# Sensor_Cameralink_TRX.net
KiCad netlist of a schematic drawn in EAGLE
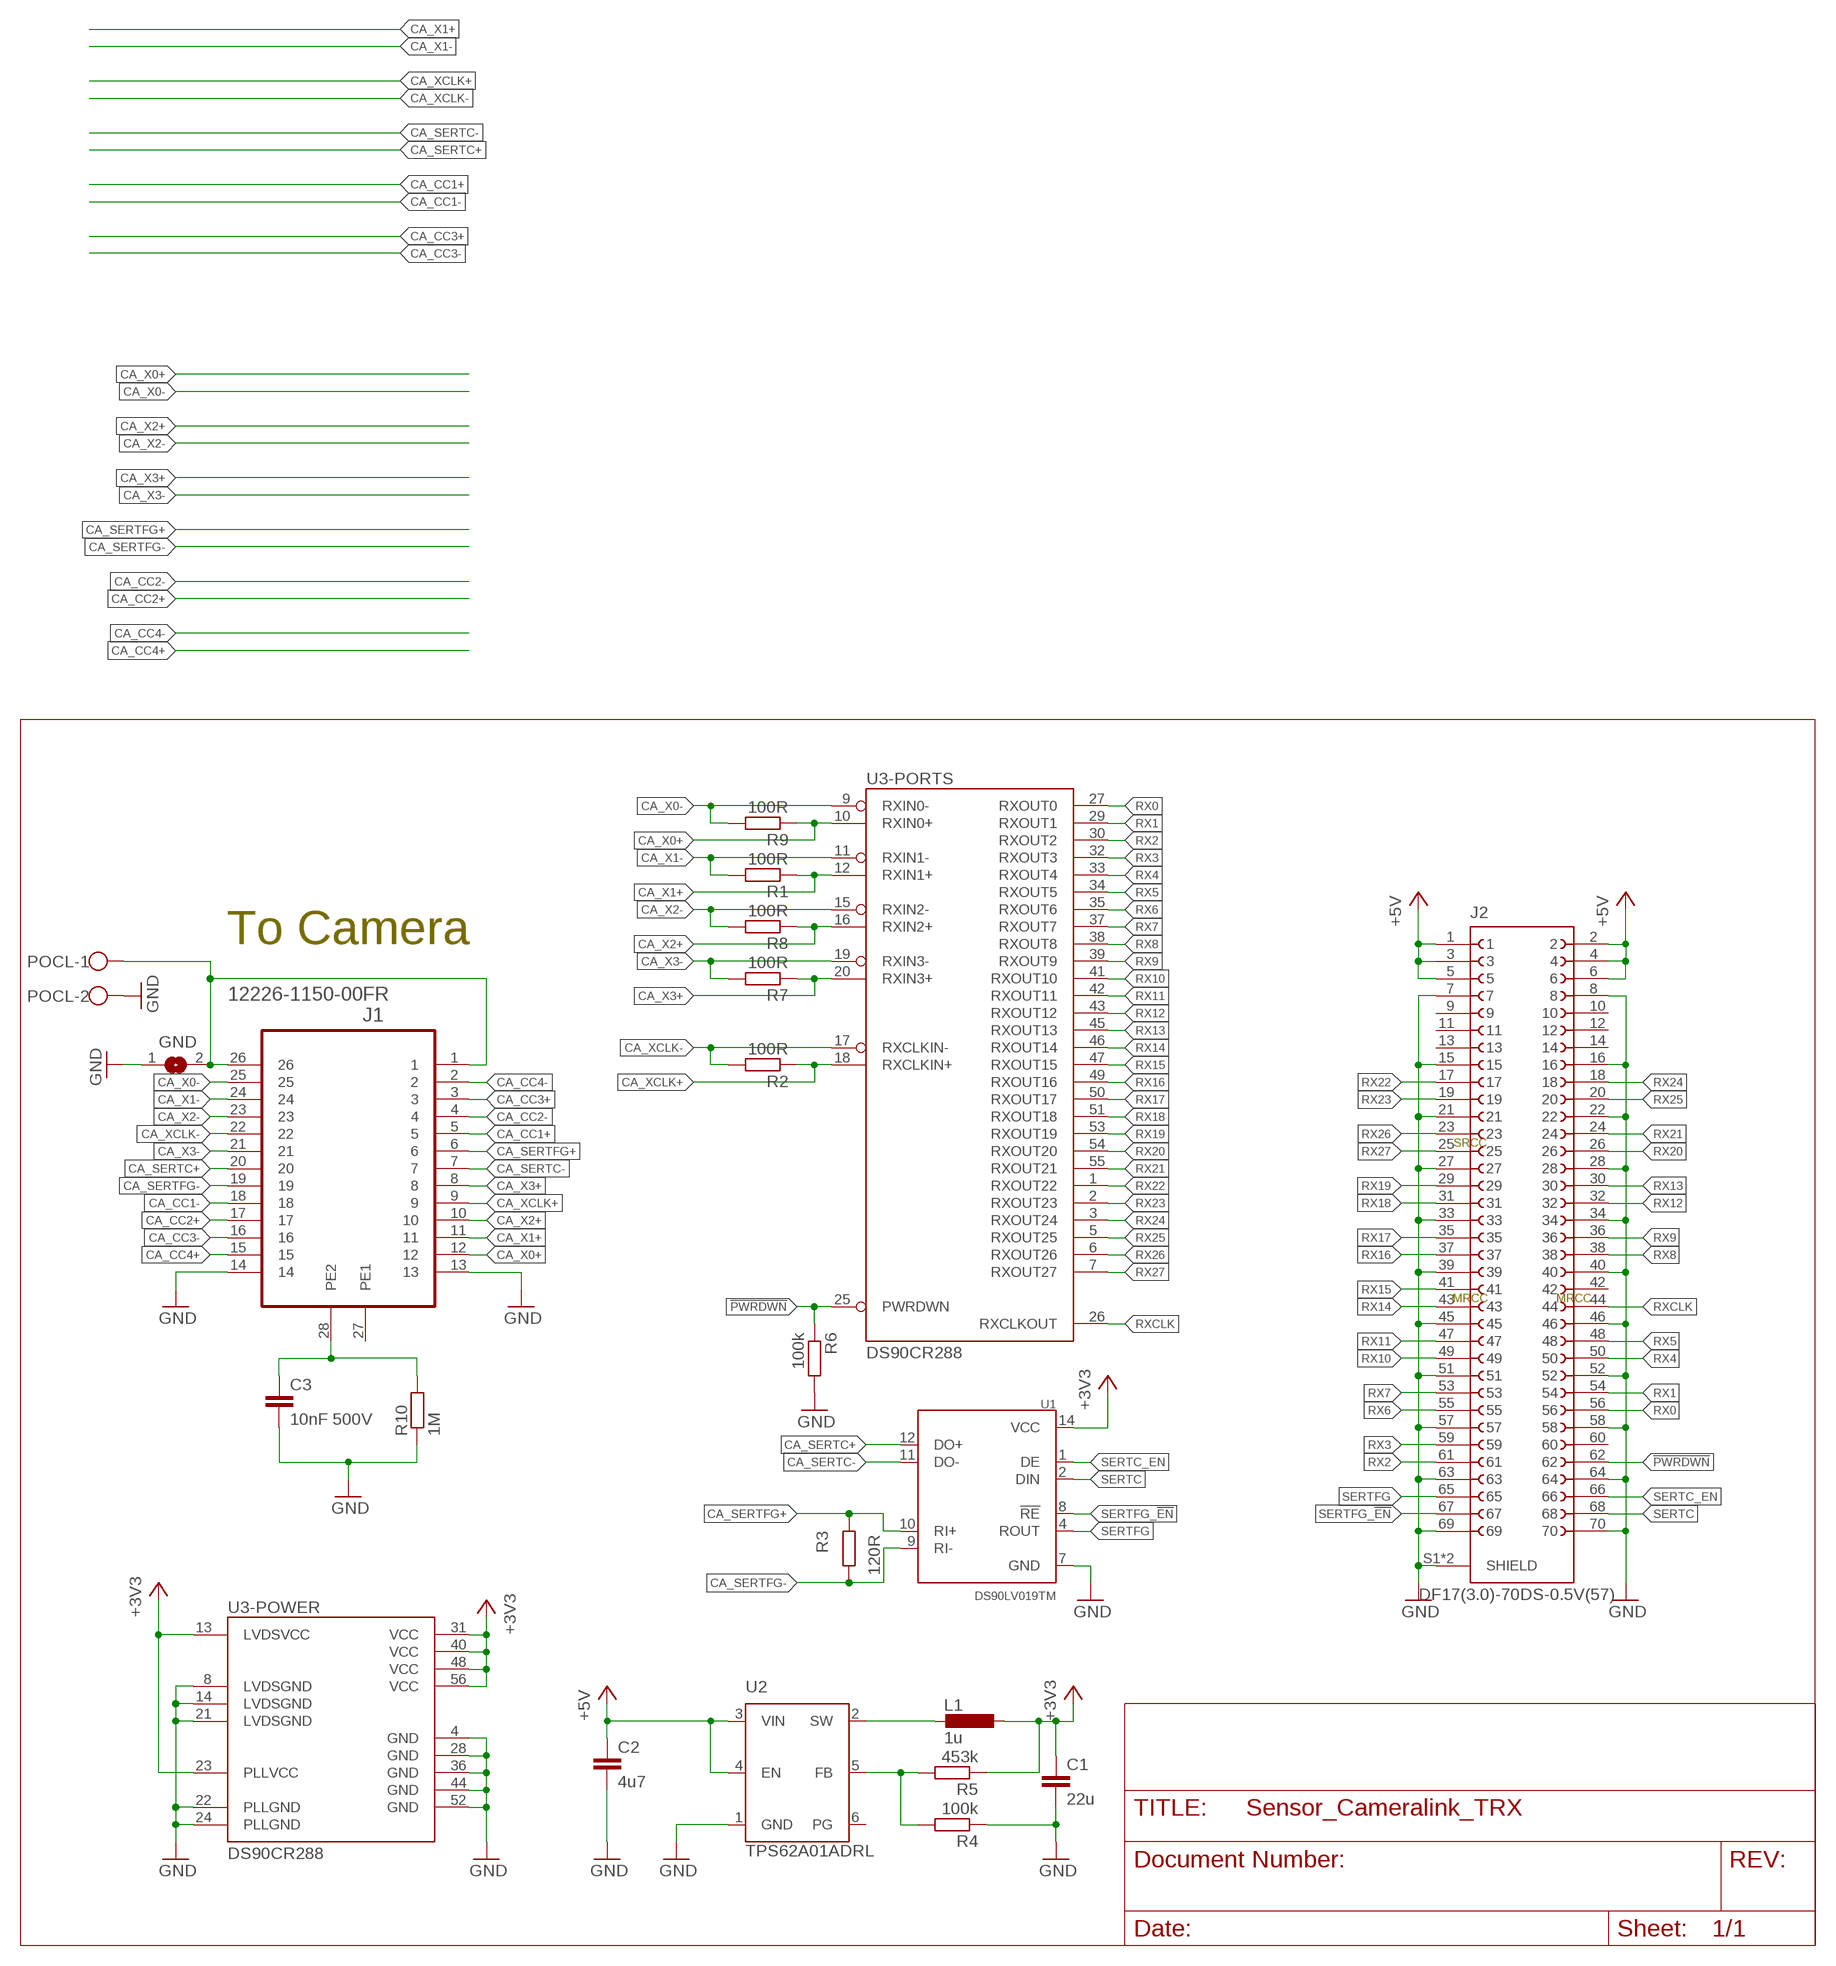
[diagram p0: schematic, sheet 1]

(export (version "E")
  (design (tool "Eeschema 10.0.6"))
  (components
    (comp (ref "C1")
      (value "22u")
      (footprint "eagle-import:C0603")
      (libsource (lib "eagle-import") (part "C-EUC0603"))
    )
    (comp (ref "C2")
      (value "4u7")
      (footprint "eagle-import:C0603")
      (libsource (lib "eagle-import") (part "C-EUC0603"))
    )
    (comp (ref "C3")
      (value "10nF 500V")
      (footprint "eagle-import:C0805")
      (libsource (lib "eagle-import") (part "C-EUC0805"))
    )
    (comp (ref "GND") (value "SJ") (footprint "eagle-import:SJ") (libsource (lib "eagle-import") (part "SJ")))
    (comp (ref "J1")
      (value "12226-1150-00FR")
      (footprint "eagle-import:3M_12226-1150-00FR")
      (libsource (lib "eagle-import") (part "12226-1150-00FR"))
    )
    (comp (ref "J2")
      (value "DF17(3.0)-70DS-0.5V(57)")
      (footprint "eagle-import:DF17(3.0)-70DS-0.5V(57)")
      (libsource (lib "eagle-import") (part "DF17(3.0)-70DS-0.5V(57)"))
    )
    (comp (ref "L1")
      (value "1u")
      (footprint "eagle-import:L1008")
      (fields (field (name "MPN") "LQM2HPN1R0MG0L"))
      (libsource (lib "eagle-import") (part "L-EU1008"))
    )
    (comp (ref "POCL")
      (value "W237-102")
      (footprint "eagle-import:W237-102")
      (fields (field (name "MPN") "237-102"))
      (libsource (lib "eagle-import") (part "W237-102"))
    )
    (comp (ref "R1")
      (value "100R")
      (footprint "eagle-import:R0402")
      (libsource (lib "eagle-import") (part "R-EU_R0402"))
    )
    (comp (ref "R2")
      (value "100R")
      (footprint "eagle-import:R0402")
      (libsource (lib "eagle-import") (part "R-EU_R0402"))
    )
    (comp (ref "R3")
      (value "120R")
      (footprint "eagle-import:R0402")
      (libsource (lib "eagle-import") (part "R-EU_R0402"))
    )
    (comp (ref "R4")
      (value "100k")
      (footprint "eagle-import:R0402")
      (libsource (lib "eagle-import") (part "R-EU_R0402"))
    )
    (comp (ref "R5")
      (value "453k")
      (footprint "eagle-import:R0402")
      (libsource (lib "eagle-import") (part "R-EU_R0402"))
    )
    (comp (ref "R6")
      (value "100k")
      (footprint "eagle-import:R0402")
      (libsource (lib "eagle-import") (part "R-EU_R0402"))
    )
    (comp (ref "R7")
      (value "100R")
      (footprint "eagle-import:R0402")
      (libsource (lib "eagle-import") (part "R-EU_R0402"))
    )
    (comp (ref "R8")
      (value "100R")
      (footprint "eagle-import:R0402")
      (libsource (lib "eagle-import") (part "R-EU_R0402"))
    )
    (comp (ref "R9")
      (value "100R")
      (footprint "eagle-import:R0402")
      (libsource (lib "eagle-import") (part "R-EU_R0402"))
    )
    (comp (ref "R10")
      (value "1M")
      (footprint "eagle-import:R0805")
      (libsource (lib "eagle-import") (part "resistor_R-EU_R0805"))
    )
    (comp (ref "U1")
      (value "DS90LV019TM")
      (footprint "eagle-import:SO-14")
      (libsource (lib "eagle-import") (part "DS90LV019TM"))
    )
    (comp (ref "U2")
      (value "TPS62A01ADRL")
      (footprint "eagle-import:SOTFL50P160X60-6N")
      (fields (field (name "MANUFACTURER_PART_NUMBER") "TPS62A01ADRLR"))
      (libsource (lib "eagle-import") (part "TPS62A01ADRL"))
    )
    (comp (ref "U3")
      (value "DS90CR288")
      (footprint "eagle-import:HTSSOP56")
      (libsource (lib "eagle-import") (part "DS90CR288"))
    )
  )
  (nets
    (net (code "1") (name "+3V3") (class "Default")
      (node (ref "C1") (pin "1") (pinfunction "1_1") (pintype "passive"))
      (node (ref "L1") (pin "1") (pinfunction "1_1") (pintype "passive"))
      (node (ref "R5") (pin "1") (pinfunction "1_1") (pintype "passive"))
      (node (ref "U1") (pin "14") (pinfunction "VCC_14") (pintype "power_in"))
      (node (ref "U3") (pin "13") (pinfunction "LVDSVCC_13") (pintype "bidirectional"))
      (node (ref "U3") (pin "23") (pinfunction "PLLVCC_23") (pintype "bidirectional"))
      (node (ref "U3") (pin "31") (pinfunction "VCC_31") (pintype "bidirectional"))
      (node (ref "U3") (pin "40") (pinfunction "VCC_40") (pintype "bidirectional"))
      (node (ref "U3") (pin "48") (pinfunction "VCC_48") (pintype "bidirectional"))
      (node (ref "U3") (pin "56") (pinfunction "VCC_56") (pintype "bidirectional"))
    )
    (net (code "2") (name "+5V") (class "Default")
      (node (ref "C2") (pin "1") (pinfunction "1_1") (pintype "passive"))
      (node (ref "J2") (pin "1") (pinfunction "1_1") (pintype "passive"))
      (node (ref "J2") (pin "2") (pinfunction "2_2") (pintype "passive"))
      (node (ref "J2") (pin "3") (pinfunction "3_3") (pintype "passive"))
      (node (ref "J2") (pin "4") (pinfunction "4_4") (pintype "passive"))
      (node (ref "J2") (pin "5") (pinfunction "5_5") (pintype "passive"))
      (node (ref "J2") (pin "6") (pinfunction "6_6") (pintype "passive"))
      (node (ref "U2") (pin "3") (pinfunction "VIN_3") (pintype "bidirectional"))
      (node (ref "U2") (pin "4") (pinfunction "EN_4") (pintype "bidirectional"))
    )
    (net (code "3") (name "/SERTFG_~{EN}") (class "Default")
      (node (ref "J2") (pin "67") (pinfunction "67_67") (pintype "passive"))
      (node (ref "U1") (pin "8") (pinfunction "~{RE}_8") (pintype "input"))
    )
    (net (code "4") (name "/~{PWRDWN}") (class "Default")
      (node (ref "J2") (pin "62") (pinfunction "62_62") (pintype "passive"))
      (node (ref "R6") (pin "1") (pinfunction "1_1") (pintype "passive"))
      (node (ref "U3") (pin "25") (pinfunction "PWRDWN_25") (pintype "bidirectional"))
    )
    (net (code "5") (name "CA_CC1+") (class "Default")
      (node (ref "J1") (pin "5") (pinfunction "5_5") (pintype "passive"))
    )
    (net (code "6") (name "CA_CC1-") (class "Default")
      (node (ref "J1") (pin "18") (pinfunction "18_18") (pintype "passive"))
    )
    (net (code "7") (name "CA_CC2+") (class "Default")
      (node (ref "J1") (pin "17") (pinfunction "17_17") (pintype "passive"))
    )
    (net (code "8") (name "CA_CC2-") (class "Default")
      (node (ref "J1") (pin "4") (pinfunction "4_4") (pintype "passive"))
    )
    (net (code "9") (name "CA_CC3+") (class "Default")
      (node (ref "J1") (pin "3") (pinfunction "3_3") (pintype "passive"))
    )
    (net (code "10") (name "CA_CC3-") (class "Default")
      (node (ref "J1") (pin "16") (pinfunction "16_16") (pintype "passive"))
    )
    (net (code "11") (name "CA_CC4+") (class "Default")
      (node (ref "J1") (pin "15") (pinfunction "15_15") (pintype "passive"))
    )
    (net (code "12") (name "CA_CC4-") (class "Default")
      (node (ref "J1") (pin "2") (pinfunction "2_2") (pintype "passive"))
    )
    (net (code "13") (name "CA_SERTC+") (class "Default")
      (node (ref "J1") (pin "20") (pinfunction "20_20") (pintype "passive"))
      (node (ref "U1") (pin "12") (pinfunction "DO+_12") (pintype "output"))
    )
    (net (code "14") (name "CA_SERTC-") (class "Default")
      (node (ref "J1") (pin "7") (pinfunction "7_7") (pintype "passive"))
      (node (ref "U1") (pin "11") (pinfunction "DO-_11") (pintype "output"))
    )
    (net (code "15") (name "CA_SERTFG+") (class "Default")
      (node (ref "J1") (pin "6") (pinfunction "6_6") (pintype "passive"))
      (node (ref "R3") (pin "1") (pinfunction "1_1") (pintype "passive"))
      (node (ref "U1") (pin "10") (pinfunction "RI+_10") (pintype "input"))
    )
    (net (code "16") (name "CA_SERTFG-") (class "Default")
      (node (ref "J1") (pin "19") (pinfunction "19_19") (pintype "passive"))
      (node (ref "R3") (pin "2") (pinfunction "2_2") (pintype "passive"))
      (node (ref "U1") (pin "9") (pinfunction "RI-_9") (pintype "input"))
    )
    (net (code "17") (name "CA_X0+") (class "Default")
      (node (ref "J1") (pin "12") (pinfunction "12_12") (pintype "passive"))
      (node (ref "R9") (pin "1") (pinfunction "1_1") (pintype "passive"))
      (node (ref "U3") (pin "10") (pinfunction "RXIN0+_10") (pintype "bidirectional"))
    )
    (net (code "18") (name "CA_X0-") (class "Default")
      (node (ref "J1") (pin "25") (pinfunction "25_25") (pintype "passive"))
      (node (ref "R9") (pin "2") (pinfunction "2_2") (pintype "passive"))
      (node (ref "U3") (pin "9") (pinfunction "RXIN0-_9") (pintype "bidirectional"))
    )
    (net (code "19") (name "CA_X1+") (class "Default")
      (node (ref "J1") (pin "11") (pinfunction "11_11") (pintype "passive"))
      (node (ref "R1") (pin "1") (pinfunction "1_1") (pintype "passive"))
      (node (ref "U3") (pin "12") (pinfunction "RXIN1+_12") (pintype "bidirectional"))
    )
    (net (code "20") (name "CA_X1-") (class "Default")
      (node (ref "J1") (pin "24") (pinfunction "24_24") (pintype "passive"))
      (node (ref "R1") (pin "2") (pinfunction "2_2") (pintype "passive"))
      (node (ref "U3") (pin "11") (pinfunction "RXIN1-_11") (pintype "bidirectional"))
    )
    (net (code "21") (name "CA_X2+") (class "Default")
      (node (ref "J1") (pin "10") (pinfunction "10_10") (pintype "passive"))
      (node (ref "R8") (pin "1") (pinfunction "1_1") (pintype "passive"))
      (node (ref "U3") (pin "16") (pinfunction "RXIN2+_16") (pintype "bidirectional"))
    )
    (net (code "22") (name "CA_X2-") (class "Default")
      (node (ref "J1") (pin "23") (pinfunction "23_23") (pintype "passive"))
      (node (ref "R8") (pin "2") (pinfunction "2_2") (pintype "passive"))
      (node (ref "U3") (pin "15") (pinfunction "RXIN2-_15") (pintype "bidirectional"))
    )
    (net (code "23") (name "CA_X3+") (class "Default")
      (node (ref "J1") (pin "8") (pinfunction "8_8") (pintype "passive"))
      (node (ref "R7") (pin "1") (pinfunction "1_1") (pintype "passive"))
      (node (ref "U3") (pin "20") (pinfunction "RXIN3+_20") (pintype "bidirectional"))
    )
    (net (code "24") (name "CA_X3-") (class "Default")
      (node (ref "J1") (pin "21") (pinfunction "21_21") (pintype "passive"))
      (node (ref "R7") (pin "2") (pinfunction "2_2") (pintype "passive"))
      (node (ref "U3") (pin "19") (pinfunction "RXIN3-_19") (pintype "bidirectional"))
    )
    (net (code "25") (name "CA_XCLK+") (class "Default")
      (node (ref "J1") (pin "9") (pinfunction "9_9") (pintype "passive"))
      (node (ref "R2") (pin "1") (pinfunction "1_1") (pintype "passive"))
      (node (ref "U3") (pin "18") (pinfunction "RXCLKIN+_18") (pintype "bidirectional"))
    )
    (net (code "26") (name "CA_XCLK-") (class "Default")
      (node (ref "J1") (pin "22") (pinfunction "22_22") (pintype "passive"))
      (node (ref "R2") (pin "2") (pinfunction "2_2") (pintype "passive"))
      (node (ref "U3") (pin "17") (pinfunction "RXCLKIN-_17") (pintype "bidirectional"))
    )
    (net (code "27") (name "GND") (class "Default")
      (node (ref "C1") (pin "2") (pinfunction "2_2") (pintype "passive"))
      (node (ref "C2") (pin "2") (pinfunction "2_2") (pintype "passive"))
      (node (ref "C3") (pin "2") (pinfunction "2_2") (pintype "passive"))
      (node (ref "GND") (pin "1") (pinfunction "1_1") (pintype "passive"))
      (node (ref "J1") (pin "13") (pinfunction "13_13") (pintype "passive"))
      (node (ref "J1") (pin "14") (pinfunction "14_14") (pintype "passive"))
      (node (ref "J2") (pin "15") (pinfunction "15_15") (pintype "passive"))
      (node (ref "J2") (pin "16") (pinfunction "16_16") (pintype "passive"))
      (node (ref "J2") (pin "21") (pinfunction "21_21") (pintype "passive"))
      (node (ref "J2") (pin "22") (pinfunction "22_22") (pintype "passive"))
      (node (ref "J2") (pin "27") (pinfunction "27_27") (pintype "passive"))
      (node (ref "J2") (pin "28") (pinfunction "28_28") (pintype "passive"))
      (node (ref "J2") (pin "33") (pinfunction "33_33") (pintype "passive"))
      (node (ref "J2") (pin "34") (pinfunction "34_34") (pintype "passive"))
      (node (ref "J2") (pin "39") (pinfunction "39_39") (pintype "passive"))
      (node (ref "J2") (pin "40") (pinfunction "40_40") (pintype "passive"))
      (node (ref "J2") (pin "45") (pinfunction "45_45") (pintype "passive"))
      (node (ref "J2") (pin "46") (pinfunction "46_46") (pintype "passive"))
      (node (ref "J2") (pin "51") (pinfunction "51_51") (pintype "passive"))
      (node (ref "J2") (pin "52") (pinfunction "52_52") (pintype "passive"))
      (node (ref "J2") (pin "57") (pinfunction "57_57") (pintype "passive"))
      (node (ref "J2") (pin "58") (pinfunction "58_58") (pintype "passive"))
      (node (ref "J2") (pin "63") (pinfunction "63_63") (pintype "passive"))
      (node (ref "J2") (pin "64") (pinfunction "64_64") (pintype "passive"))
      (node (ref "J2") (pin "69") (pinfunction "69_69") (pintype "passive"))
      (node (ref "J2") (pin "7") (pinfunction "7_7") (pintype "passive"))
      (node (ref "J2") (pin "70") (pinfunction "70_70") (pintype "passive"))
      (node (ref "J2") (pin "8") (pinfunction "8_8") (pintype "passive"))
      (node (ref "J2") (pin "S1") (pinfunction "SHIELD_S1") (pintype "passive"))
      (node (ref "J2") (pin "S2") (pinfunction "SHIELD_S2") (pintype "passive"))
      (node (ref "POCL") (pin "2") (pinfunction "KL_2") (pintype "passive"))
      (node (ref "R10") (pin "1") (pinfunction "1_1") (pintype "passive"))
      (node (ref "R4") (pin "1") (pinfunction "1_1") (pintype "passive"))
      (node (ref "R6") (pin "2") (pinfunction "2_2") (pintype "passive"))
      (node (ref "U1") (pin "7") (pinfunction "GND_7") (pintype "power_in"))
      (node (ref "U2") (pin "1") (pinfunction "GND_1") (pintype "bidirectional"))
      (node (ref "U3") (pin "14") (pinfunction "LVDSGND_14") (pintype "bidirectional"))
      (node (ref "U3") (pin "21") (pinfunction "LVDSGND_21") (pintype "bidirectional"))
      (node (ref "U3") (pin "22") (pinfunction "PLLGND_22") (pintype "bidirectional"))
      (node (ref "U3") (pin "24") (pinfunction "PLLGND_24") (pintype "bidirectional"))
      (node (ref "U3") (pin "28") (pinfunction "GND_28") (pintype "bidirectional"))
      (node (ref "U3") (pin "36") (pinfunction "GND_36") (pintype "bidirectional"))
      (node (ref "U3") (pin "4") (pinfunction "GND_4") (pintype "bidirectional"))
      (node (ref "U3") (pin "44") (pinfunction "GND_44") (pintype "bidirectional"))
      (node (ref "U3") (pin "52") (pinfunction "GND_52") (pintype "bidirectional"))
      (node (ref "U3") (pin "8") (pinfunction "LVDSGND_8") (pintype "bidirectional"))
    )
    (net (code "28") (name "Net-(J1-PE2)") (class "Default")
      (node (ref "C3") (pin "1") (pinfunction "1_1") (pintype "passive"))
      (node (ref "J1") (pin "28") (pinfunction "PE2_28") (pintype "bidirectional"))
      (node (ref "R10") (pin "2") (pinfunction "2_2") (pintype "passive"))
    )
    (net (code "29") (name "Net-(POCLA-KL)") (class "Default")
      (node (ref "GND") (pin "2") (pinfunction "2_2") (pintype "passive"))
      (node (ref "J1") (pin "1") (pinfunction "1_1") (pintype "passive"))
      (node (ref "J1") (pin "26") (pinfunction "26_26") (pintype "passive"))
      (node (ref "POCL") (pin "1") (pinfunction "KL_1") (pintype "passive"))
    )
    (net (code "30") (name "Net-(U2-FB)") (class "Default")
      (node (ref "R4") (pin "2") (pinfunction "2_2") (pintype "passive"))
      (node (ref "R5") (pin "2") (pinfunction "2_2") (pintype "passive"))
      (node (ref "U2") (pin "5") (pinfunction "FB_5") (pintype "bidirectional"))
    )
    (net (code "31") (name "Net-(U2-SW)") (class "Default")
      (node (ref "L1") (pin "2") (pinfunction "2_2") (pintype "passive"))
      (node (ref "U2") (pin "2") (pinfunction "SW_2") (pintype "bidirectional"))
    )
    (net (code "32") (name "RX0") (class "Default")
      (node (ref "J2") (pin "56") (pinfunction "56_56") (pintype "passive"))
      (node (ref "U3") (pin "27") (pinfunction "RXOUT0_27") (pintype "bidirectional"))
    )
    (net (code "33") (name "RX1") (class "Default")
      (node (ref "J2") (pin "54") (pinfunction "54_54") (pintype "passive"))
      (node (ref "U3") (pin "29") (pinfunction "RXOUT1_29") (pintype "bidirectional"))
    )
    (net (code "34") (name "RX2") (class "Default")
      (node (ref "J2") (pin "61") (pinfunction "61_61") (pintype "passive"))
      (node (ref "U3") (pin "30") (pinfunction "RXOUT2_30") (pintype "bidirectional"))
    )
    (net (code "35") (name "RX3") (class "Default")
      (node (ref "J2") (pin "59") (pinfunction "59_59") (pintype "passive"))
      (node (ref "U3") (pin "32") (pinfunction "RXOUT3_32") (pintype "bidirectional"))
    )
    (net (code "36") (name "RX4") (class "Default")
      (node (ref "J2") (pin "50") (pinfunction "50_50") (pintype "passive"))
      (node (ref "U3") (pin "33") (pinfunction "RXOUT4_33") (pintype "bidirectional"))
    )
    (net (code "37") (name "RX5") (class "Default")
      (node (ref "J2") (pin "48") (pinfunction "48_48") (pintype "passive"))
      (node (ref "U3") (pin "34") (pinfunction "RXOUT5_34") (pintype "bidirectional"))
    )
    (net (code "38") (name "RX6") (class "Default")
      (node (ref "J2") (pin "55") (pinfunction "55_55") (pintype "passive"))
      (node (ref "U3") (pin "35") (pinfunction "RXOUT6_35") (pintype "bidirectional"))
    )
    (net (code "39") (name "RX7") (class "Default")
      (node (ref "J2") (pin "53") (pinfunction "53_53") (pintype "passive"))
      (node (ref "U3") (pin "37") (pinfunction "RXOUT7_37") (pintype "bidirectional"))
    )
    (net (code "40") (name "RX8") (class "Default")
      (node (ref "J2") (pin "38") (pinfunction "38_38") (pintype "passive"))
      (node (ref "U3") (pin "38") (pinfunction "RXOUT8_38") (pintype "bidirectional"))
    )
    (net (code "41") (name "RX9") (class "Default")
      (node (ref "J2") (pin "36") (pinfunction "36_36") (pintype "passive"))
      (node (ref "U3") (pin "39") (pinfunction "RXOUT9_39") (pintype "bidirectional"))
    )
    (net (code "42") (name "RX10") (class "Default")
      (node (ref "J2") (pin "49") (pinfunction "49_49") (pintype "passive"))
      (node (ref "U3") (pin "41") (pinfunction "RXOUT10_41") (pintype "bidirectional"))
    )
    (net (code "43") (name "RX11") (class "Default")
      (node (ref "J2") (pin "47") (pinfunction "47_47") (pintype "passive"))
      (node (ref "U3") (pin "42") (pinfunction "RXOUT11_42") (pintype "bidirectional"))
    )
    (net (code "44") (name "RX12") (class "Default")
      (node (ref "J2") (pin "32") (pinfunction "32_32") (pintype "passive"))
      (node (ref "U3") (pin "43") (pinfunction "RXOUT12_43") (pintype "bidirectional"))
    )
    (net (code "45") (name "RX13") (class "Default")
      (node (ref "J2") (pin "30") (pinfunction "30_30") (pintype "passive"))
      (node (ref "U3") (pin "45") (pinfunction "RXOUT13_45") (pintype "bidirectional"))
    )
    (net (code "46") (name "RX14") (class "Default")
      (node (ref "J2") (pin "43") (pinfunction "43_43") (pintype "passive"))
      (node (ref "U3") (pin "46") (pinfunction "RXOUT14_46") (pintype "bidirectional"))
    )
    (net (code "47") (name "RX15") (class "Default")
      (node (ref "J2") (pin "41") (pinfunction "41_41") (pintype "passive"))
      (node (ref "U3") (pin "47") (pinfunction "RXOUT15_47") (pintype "bidirectional"))
    )
    (net (code "48") (name "RX16") (class "Default")
      (node (ref "J2") (pin "37") (pinfunction "37_37") (pintype "passive"))
      (node (ref "U3") (pin "49") (pinfunction "RXOUT16_49") (pintype "bidirectional"))
    )
    (net (code "49") (name "RX17") (class "Default")
      (node (ref "J2") (pin "35") (pinfunction "35_35") (pintype "passive"))
      (node (ref "U3") (pin "50") (pinfunction "RXOUT17_50") (pintype "bidirectional"))
    )
    (net (code "50") (name "RX18") (class "Default")
      (node (ref "J2") (pin "31") (pinfunction "31_31") (pintype "passive"))
      (node (ref "U3") (pin "51") (pinfunction "RXOUT18_51") (pintype "bidirectional"))
    )
    (net (code "51") (name "RX19") (class "Default")
      (node (ref "J2") (pin "29") (pinfunction "29_29") (pintype "passive"))
      (node (ref "U3") (pin "53") (pinfunction "RXOUT19_53") (pintype "bidirectional"))
    )
    (net (code "52") (name "RX20") (class "Default")
      (node (ref "J2") (pin "26") (pinfunction "26_26") (pintype "passive"))
      (node (ref "U3") (pin "54") (pinfunction "RXOUT20_54") (pintype "bidirectional"))
    )
    (net (code "53") (name "RX21") (class "Default")
      (node (ref "J2") (pin "24") (pinfunction "24_24") (pintype "passive"))
      (node (ref "U3") (pin "55") (pinfunction "RXOUT21_55") (pintype "bidirectional"))
    )
    (net (code "54") (name "RX22") (class "Default")
      (node (ref "J2") (pin "17") (pinfunction "17_17") (pintype "passive"))
      (node (ref "U3") (pin "1") (pinfunction "RXOUT22_1") (pintype "bidirectional"))
    )
    (net (code "55") (name "RX23") (class "Default")
      (node (ref "J2") (pin "19") (pinfunction "19_19") (pintype "passive"))
      (node (ref "U3") (pin "2") (pinfunction "RXOUT23_2") (pintype "bidirectional"))
    )
    (net (code "56") (name "RX24") (class "Default")
      (node (ref "J2") (pin "18") (pinfunction "18_18") (pintype "passive"))
      (node (ref "U3") (pin "3") (pinfunction "RXOUT24_3") (pintype "bidirectional"))
    )
    (net (code "57") (name "RX25") (class "Default")
      (node (ref "J2") (pin "20") (pinfunction "20_20") (pintype "passive"))
      (node (ref "U3") (pin "5") (pinfunction "RXOUT25_5") (pintype "bidirectional"))
    )
    (net (code "58") (name "RX26") (class "Default")
      (node (ref "J2") (pin "23") (pinfunction "23_23") (pintype "passive"))
      (node (ref "U3") (pin "6") (pinfunction "RXOUT26_6") (pintype "bidirectional"))
    )
    (net (code "59") (name "RX27") (class "Default")
      (node (ref "J2") (pin "25") (pinfunction "25_25") (pintype "passive"))
      (node (ref "U3") (pin "7") (pinfunction "RXOUT27_7") (pintype "bidirectional"))
    )
    (net (code "60") (name "RXCLK") (class "Default")
      (node (ref "J2") (pin "44") (pinfunction "44_44") (pintype "passive"))
      (node (ref "U3") (pin "26") (pinfunction "RXCLKOUT_26") (pintype "bidirectional"))
    )
    (net (code "61") (name "SERTC") (class "Default")
      (node (ref "J2") (pin "68") (pinfunction "68_68") (pintype "passive"))
      (node (ref "U1") (pin "2") (pinfunction "DIN_2") (pintype "input"))
    )
    (net (code "62") (name "SERTC_EN") (class "Default")
      (node (ref "J2") (pin "66") (pinfunction "66_66") (pintype "passive"))
      (node (ref "U1") (pin "1") (pinfunction "DE_1") (pintype "input"))
    )
    (net (code "63") (name "SERTFG") (class "Default")
      (node (ref "J2") (pin "65") (pinfunction "65_65") (pintype "passive"))
      (node (ref "U1") (pin "4") (pinfunction "ROUT_4") (pintype "output"))
    )
    (net (code "64") (name "unconnected-(J1-PE1-Pad27)") (class "Default")
      (node (ref "J1") (pin "27") (pinfunction "PE1_27") (pintype "bidirectional"))
    )
    (net (code "65") (name "unconnected-(J2-Pad9)") (class "Default")
      (node (ref "J2") (pin "9") (pinfunction "9_9") (pintype "passive"))
    )
    (net (code "66") (name "unconnected-(J2-Pad10)") (class "Default")
      (node (ref "J2") (pin "10") (pinfunction "10_10") (pintype "passive"))
    )
    (net (code "67") (name "unconnected-(J2-Pad11)") (class "Default")
      (node (ref "J2") (pin "11") (pinfunction "11_11") (pintype "passive"))
    )
    (net (code "68") (name "unconnected-(J2-Pad12)") (class "Default")
      (node (ref "J2") (pin "12") (pinfunction "12_12") (pintype "passive"))
    )
    (net (code "69") (name "unconnected-(J2-Pad13)") (class "Default")
      (node (ref "J2") (pin "13") (pinfunction "13_13") (pintype "passive"))
    )
    (net (code "70") (name "unconnected-(J2-Pad14)") (class "Default")
      (node (ref "J2") (pin "14") (pinfunction "14_14") (pintype "passive"))
    )
    (net (code "71") (name "unconnected-(J2-Pad42)") (class "Default")
      (node (ref "J2") (pin "42") (pinfunction "42_42") (pintype "passive"))
    )
    (net (code "72") (name "unconnected-(J2-Pad60)") (class "Default")
      (node (ref "J2") (pin "60") (pinfunction "60_60") (pintype "passive"))
    )
    (net (code "73") (name "unconnected-(U2-PG-Pad6)") (class "Default")
      (node (ref "U2") (pin "6") (pinfunction "PG_6") (pintype "bidirectional"))
    )
  )
)
